# M_A_base.net
KiCad netlist of a schematic drawn in EAGLE
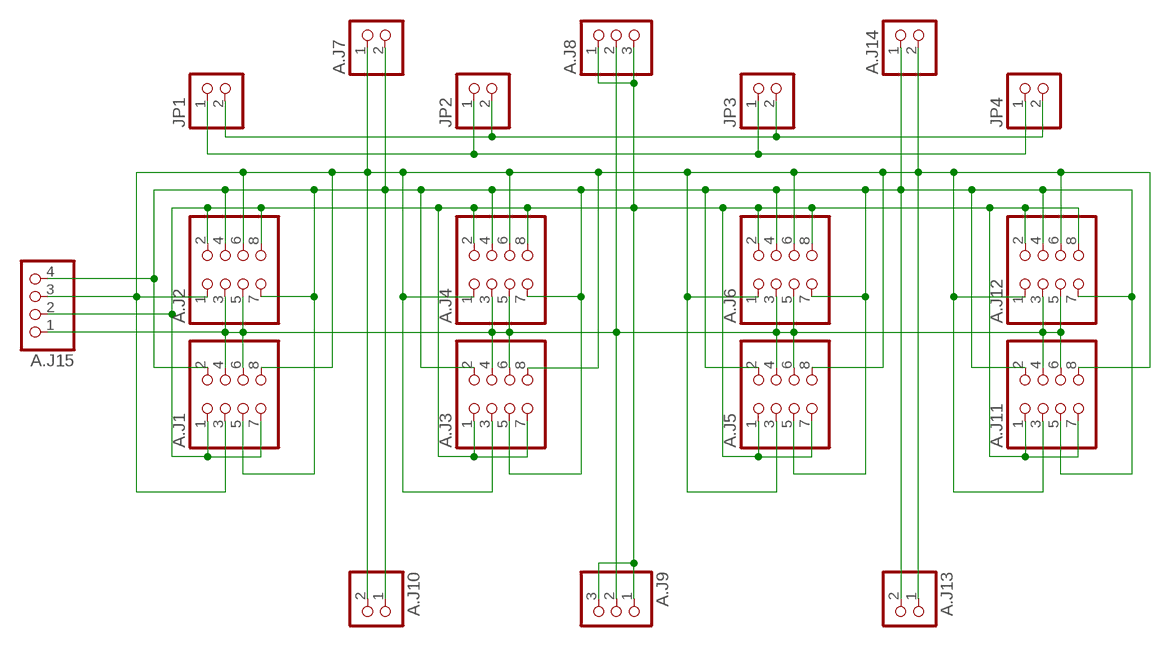
[diagram p0: schematic, sheet 1]

(export (version "E")
  (design (tool "Eeschema 10.0.6"))
  (components
    (comp (ref "A.J1")
      (value "PINHD-2X4")
      (footprint "eagle-import:2X04")
      (libsource (lib "eagle-import") (part "PINHD-2X4"))
    )
    (comp (ref "A.J2")
      (value "PINHD-2X4")
      (footprint "eagle-import:2X04")
      (libsource (lib "eagle-import") (part "PINHD-2X4"))
    )
    (comp (ref "A.J3")
      (value "PINHD-2X4")
      (footprint "eagle-import:2X04")
      (libsource (lib "eagle-import") (part "PINHD-2X4"))
    )
    (comp (ref "A.J4")
      (value "PINHD-2X4")
      (footprint "eagle-import:2X04")
      (libsource (lib "eagle-import") (part "PINHD-2X4"))
    )
    (comp (ref "A.J5")
      (value "PINHD-2X4")
      (footprint "eagle-import:2X04")
      (libsource (lib "eagle-import") (part "PINHD-2X4"))
    )
    (comp (ref "A.J6")
      (value "PINHD-2X4")
      (footprint "eagle-import:2X04")
      (libsource (lib "eagle-import") (part "PINHD-2X4"))
    )
    (comp (ref "A.J7")
      (value "PINHD-1X2/90")
      (footprint "eagle-import:1X02_90")
      (libsource (lib "eagle-import") (part "PINHD-1X2/90"))
    )
    (comp (ref "A.J8")
      (value "PINHD-1X3/90")
      (footprint "eagle-import:1X03_90")
      (libsource (lib "eagle-import") (part "PINHD-1X3/90"))
    )
    (comp (ref "A.J9")
      (value "PINHD-1X31X03/90F")
      (footprint "eagle-import:1X03_90F")
      (libsource (lib "eagle-import") (part "PINHD-1X31X03/90F"))
    )
    (comp (ref "A.J10")
      (value "PINHD-1X21X02/90F")
      (footprint "eagle-import:1X02_90F")
      (libsource (lib "eagle-import") (part "PINHD-1X21X02/90F"))
    )
    (comp (ref "A.J11")
      (value "PINHD-2X4")
      (footprint "eagle-import:2X04")
      (libsource (lib "eagle-import") (part "PINHD-2X4"))
    )
    (comp (ref "A.J12")
      (value "PINHD-2X4")
      (footprint "eagle-import:2X04")
      (libsource (lib "eagle-import") (part "PINHD-2X4"))
    )
    (comp (ref "A.J13")
      (value "PINHD-1X21X02/90F")
      (footprint "eagle-import:1X02_90F")
      (libsource (lib "eagle-import") (part "PINHD-1X21X02/90F"))
    )
    (comp (ref "A.J14")
      (value "PINHD-1X2/90")
      (footprint "eagle-import:1X02_90")
      (libsource (lib "eagle-import") (part "PINHD-1X2/90"))
    )
    (comp (ref "A.J15")
      (value "PINHD-1X4")
      (footprint "eagle-import:1X04")
      (libsource (lib "eagle-import") (part "PINHD-1X4"))
    )
    (comp (ref "JP1")
      (value "PINHD-1X2")
      (footprint "eagle-import:1X02")
      (libsource (lib "eagle-import") (part "PINHD-1X2"))
    )
    (comp (ref "JP2")
      (value "PINHD-1X2")
      (footprint "eagle-import:1X02")
      (libsource (lib "eagle-import") (part "PINHD-1X2"))
    )
    (comp (ref "JP3")
      (value "PINHD-1X2")
      (footprint "eagle-import:1X02")
      (libsource (lib "eagle-import") (part "PINHD-1X2"))
    )
    (comp (ref "JP4")
      (value "PINHD-1X2")
      (footprint "eagle-import:1X02")
      (libsource (lib "eagle-import") (part "PINHD-1X2"))
    )
  )
  (nets
    (net (code "1") (name "Net-(A.J1-Pad1)") (class "Default")
      (node (ref "A.J1") (pin "1") (pinfunction "1_1") (pintype "passive"))
      (node (ref "A.J1") (pin "7") (pinfunction "7_7") (pintype "passive"))
      (node (ref "A.J11") (pin "1") (pinfunction "1_1") (pintype "passive"))
      (node (ref "A.J11") (pin "7") (pinfunction "7_7") (pintype "passive"))
      (node (ref "A.J12") (pin "2") (pinfunction "2_2") (pintype "passive"))
      (node (ref "A.J12") (pin "8") (pinfunction "8_8") (pintype "passive"))
      (node (ref "A.J15") (pin "2") (pinfunction "2_2") (pintype "passive"))
      (node (ref "A.J2") (pin "2") (pinfunction "2_2") (pintype "passive"))
      (node (ref "A.J2") (pin "8") (pinfunction "8_8") (pintype "passive"))
      (node (ref "A.J3") (pin "1") (pinfunction "1_1") (pintype "passive"))
      (node (ref "A.J3") (pin "7") (pinfunction "7_7") (pintype "passive"))
      (node (ref "A.J4") (pin "2") (pinfunction "2_2") (pintype "passive"))
      (node (ref "A.J4") (pin "8") (pinfunction "8_8") (pintype "passive"))
      (node (ref "A.J5") (pin "1") (pinfunction "1_1") (pintype "passive"))
      (node (ref "A.J5") (pin "7") (pinfunction "7_7") (pintype "passive"))
      (node (ref "A.J6") (pin "2") (pinfunction "2_2") (pintype "passive"))
      (node (ref "A.J6") (pin "8") (pinfunction "8_8") (pintype "passive"))
      (node (ref "A.J8") (pin "1") (pinfunction "1_1") (pintype "passive"))
      (node (ref "A.J8") (pin "3") (pinfunction "3_3") (pintype "passive"))
      (node (ref "A.J9") (pin "1") (pinfunction "1_1") (pintype "passive"))
      (node (ref "A.J9") (pin "3") (pinfunction "3_3") (pintype "passive"))
    )
    (net (code "2") (name "Net-(A.J1-Pad2)") (class "Default")
      (node (ref "A.J1") (pin "2") (pinfunction "2_2") (pintype "passive"))
      (node (ref "A.J1") (pin "5") (pinfunction "5_5") (pintype "passive"))
      (node (ref "A.J10") (pin "1") (pinfunction "1_1") (pintype "passive"))
      (node (ref "A.J11") (pin "2") (pinfunction "2_2") (pintype "passive"))
      (node (ref "A.J11") (pin "5") (pinfunction "5_5") (pintype "passive"))
      (node (ref "A.J12") (pin "4") (pinfunction "4_4") (pintype "passive"))
      (node (ref "A.J12") (pin "7") (pinfunction "7_7") (pintype "passive"))
      (node (ref "A.J13") (pin "2") (pinfunction "2_2") (pintype "passive"))
      (node (ref "A.J14") (pin "1") (pinfunction "1_1") (pintype "passive"))
      (node (ref "A.J15") (pin "4") (pinfunction "4_4") (pintype "passive"))
      (node (ref "A.J2") (pin "4") (pinfunction "4_4") (pintype "passive"))
      (node (ref "A.J2") (pin "7") (pinfunction "7_7") (pintype "passive"))
      (node (ref "A.J3") (pin "2") (pinfunction "2_2") (pintype "passive"))
      (node (ref "A.J3") (pin "5") (pinfunction "5_5") (pintype "passive"))
      (node (ref "A.J4") (pin "4") (pinfunction "4_4") (pintype "passive"))
      (node (ref "A.J4") (pin "7") (pinfunction "7_7") (pintype "passive"))
      (node (ref "A.J5") (pin "2") (pinfunction "2_2") (pintype "passive"))
      (node (ref "A.J5") (pin "5") (pinfunction "5_5") (pintype "passive"))
      (node (ref "A.J6") (pin "4") (pinfunction "4_4") (pintype "passive"))
      (node (ref "A.J6") (pin "7") (pinfunction "7_7") (pintype "passive"))
      (node (ref "A.J7") (pin "2") (pinfunction "2_2") (pintype "passive"))
    )
    (net (code "3") (name "Net-(A.J1-Pad3)") (class "Default")
      (node (ref "A.J1") (pin "3") (pinfunction "3_3") (pintype "passive"))
      (node (ref "A.J1") (pin "8") (pinfunction "8_8") (pintype "passive"))
      (node (ref "A.J10") (pin "2") (pinfunction "2_2") (pintype "passive"))
      (node (ref "A.J11") (pin "3") (pinfunction "3_3") (pintype "passive"))
      (node (ref "A.J11") (pin "8") (pinfunction "8_8") (pintype "passive"))
      (node (ref "A.J12") (pin "1") (pinfunction "1_1") (pintype "passive"))
      (node (ref "A.J12") (pin "6") (pinfunction "6_6") (pintype "passive"))
      (node (ref "A.J13") (pin "1") (pinfunction "1_1") (pintype "passive"))
      (node (ref "A.J14") (pin "2") (pinfunction "2_2") (pintype "passive"))
      (node (ref "A.J15") (pin "3") (pinfunction "3_3") (pintype "passive"))
      (node (ref "A.J2") (pin "1") (pinfunction "1_1") (pintype "passive"))
      (node (ref "A.J2") (pin "6") (pinfunction "6_6") (pintype "passive"))
      (node (ref "A.J3") (pin "3") (pinfunction "3_3") (pintype "passive"))
      (node (ref "A.J3") (pin "8") (pinfunction "8_8") (pintype "passive"))
      (node (ref "A.J4") (pin "1") (pinfunction "1_1") (pintype "passive"))
      (node (ref "A.J4") (pin "6") (pinfunction "6_6") (pintype "passive"))
      (node (ref "A.J5") (pin "3") (pinfunction "3_3") (pintype "passive"))
      (node (ref "A.J5") (pin "8") (pinfunction "8_8") (pintype "passive"))
      (node (ref "A.J6") (pin "1") (pinfunction "1_1") (pintype "passive"))
      (node (ref "A.J6") (pin "6") (pinfunction "6_6") (pintype "passive"))
      (node (ref "A.J7") (pin "1") (pinfunction "1_1") (pintype "passive"))
    )
    (net (code "4") (name "Net-(A.J1-Pad4)") (class "Default")
      (node (ref "A.J1") (pin "4") (pinfunction "4_4") (pintype "passive"))
      (node (ref "A.J1") (pin "6") (pinfunction "6_6") (pintype "passive"))
      (node (ref "A.J11") (pin "4") (pinfunction "4_4") (pintype "passive"))
      (node (ref "A.J11") (pin "6") (pinfunction "6_6") (pintype "passive"))
      (node (ref "A.J12") (pin "3") (pinfunction "3_3") (pintype "passive"))
      (node (ref "A.J12") (pin "5") (pinfunction "5_5") (pintype "passive"))
      (node (ref "A.J15") (pin "1") (pinfunction "1_1") (pintype "passive"))
      (node (ref "A.J2") (pin "3") (pinfunction "3_3") (pintype "passive"))
      (node (ref "A.J2") (pin "5") (pinfunction "5_5") (pintype "passive"))
      (node (ref "A.J3") (pin "4") (pinfunction "4_4") (pintype "passive"))
      (node (ref "A.J3") (pin "6") (pinfunction "6_6") (pintype "passive"))
      (node (ref "A.J4") (pin "3") (pinfunction "3_3") (pintype "passive"))
      (node (ref "A.J4") (pin "5") (pinfunction "5_5") (pintype "passive"))
      (node (ref "A.J5") (pin "4") (pinfunction "4_4") (pintype "passive"))
      (node (ref "A.J5") (pin "6") (pinfunction "6_6") (pintype "passive"))
      (node (ref "A.J6") (pin "3") (pinfunction "3_3") (pintype "passive"))
      (node (ref "A.J6") (pin "5") (pinfunction "5_5") (pintype "passive"))
      (node (ref "A.J8") (pin "2") (pinfunction "2_2") (pintype "passive"))
      (node (ref "A.J9") (pin "2") (pinfunction "2_2") (pintype "passive"))
    )
    (net (code "5") (name "Net-(JP1-Pad1)") (class "Default")
      (node (ref "JP1") (pin "1") (pinfunction "1_1") (pintype "passive"))
      (node (ref "JP2") (pin "1") (pinfunction "1_1") (pintype "passive"))
      (node (ref "JP3") (pin "1") (pinfunction "1_1") (pintype "passive"))
      (node (ref "JP4") (pin "1") (pinfunction "1_1") (pintype "passive"))
    )
    (net (code "6") (name "Net-(JP1-Pad2)") (class "Default")
      (node (ref "JP1") (pin "2") (pinfunction "2_2") (pintype "passive"))
      (node (ref "JP2") (pin "2") (pinfunction "2_2") (pintype "passive"))
      (node (ref "JP3") (pin "2") (pinfunction "2_2") (pintype "passive"))
      (node (ref "JP4") (pin "2") (pinfunction "2_2") (pintype "passive"))
    )
  )
)
